# Logic.net
KiCad netlist of a schematic drawn in Altium Designer
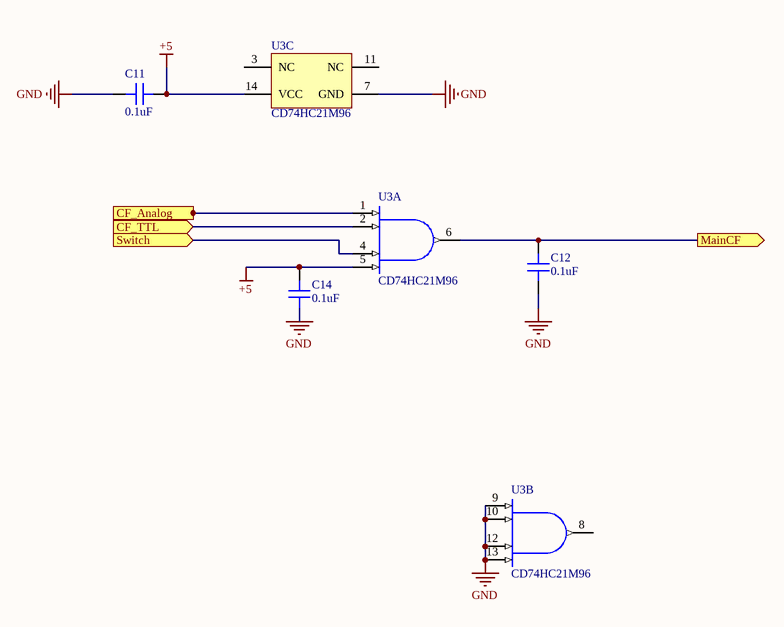
[diagram p0: Logic.SchDoc]

(export (version "E")
  (design (tool "Eeschema 10.0.6"))
  (components
    (comp (ref "C11")
      (value "0.1uF")
      (footprint "CAP 0805/2012")
      (description "CAP CER 0.1UF 25V X7R 0805")
      (fields
        (field (name "PART NUMBER") "CL21B104KACNNNC")
        (field (name "MANUFACTURER") "Samsung Electro-Mechanics America, Inc.")
      )
      (libsource (lib "Celestial Library Database") (part "Capacitor"))
    )
    (comp (ref "C12")
      (value "0.1uF")
      (footprint "CAP 0805/2012")
      (description "CAP CER 0.1UF 25V X7R 0805")
      (fields
        (field (name "PART NUMBER") "CL21B104KACNNNC")
        (field (name "MANUFACTURER") "Samsung Electro-Mechanics America, Inc.")
      )
      (libsource (lib "Celestial Library Database") (part "Capacitor"))
    )
    (comp (ref "C14")
      (value "0.1uF")
      (footprint "CAP 0805/2012")
      (description "CAP CER 0.1UF 25V X7R 0805")
      (fields
        (field (name "PART NUMBER") "CL21B104KACNNNC")
        (field (name "MANUFACTURER") "Samsung Electro-Mechanics America, Inc.")
      )
      (libsource (lib "Celestial Library Database") (part "Capacitor"))
    )
    (comp (ref "U3")
      (value "CD74HC21M96")
      (footprint "D0014A_N")
      (description "High Speed CMOS Logic Dual 4-Input AND Gates, D0014A, LARGE T&R")
      (fields
        (field (name "GENERIC PART NUMBER") "CD74HC21")
        (field (name "MANUFACTURER") "Texas Instruments")
      )
      (libsource (lib "Altium Content Vault") (part "TI-SNX4XXX21X-14"))
    )
  )
  (nets
    (net (code "1") (name "+5") (class "Default")
      (node (ref "C11") (pin "1") (pinfunction "1_1") (pintype "passive"))
      (node (ref "C14") (pin "1") (pinfunction "1_1") (pintype "passive"))
      (node (ref "U3") (pin "14") (pinfunction "VCC_14") (pintype "power_in"))
      (node (ref "U3") (pin "5") (pinfunction "1D_5") (pintype "input"))
    )
    (net (code "2") (name "/CF_Analog") (class "Default")
      (node (ref "U3") (pin "1") (pinfunction "1A_1") (pintype "input"))
    )
    (net (code "3") (name "/CF_TTL") (class "Default")
      (node (ref "U3") (pin "2") (pinfunction "1B_2") (pintype "input"))
    )
    (net (code "4") (name "/MainCF") (class "Default")
      (node (ref "C12") (pin "1") (pinfunction "1_1") (pintype "passive"))
      (node (ref "U3") (pin "6") (pinfunction "1Y_6") (pintype "output"))
    )
    (net (code "5") (name "/Switch") (class "Default")
      (node (ref "U3") (pin "4") (pinfunction "1C_4") (pintype "input"))
    )
    (net (code "6") (name "GND") (class "Default")
      (node (ref "C11") (pin "2") (pinfunction "2_2") (pintype "passive"))
      (node (ref "C12") (pin "2") (pinfunction "2_2") (pintype "passive"))
      (node (ref "C14") (pin "2") (pinfunction "2_2") (pintype "passive"))
      (node (ref "U3") (pin "10") (pinfunction "2B_10") (pintype "input"))
      (node (ref "U3") (pin "12") (pinfunction "2C_12") (pintype "input"))
      (node (ref "U3") (pin "13") (pinfunction "2D_13") (pintype "input"))
      (node (ref "U3") (pin "7") (pinfunction "GND_7") (pintype "power_in"))
      (node (ref "U3") (pin "9") (pinfunction "2A_9") (pintype "input"))
    )
    (net (code "7") (name "unconnected-(U3B-2Y-Pad8)") (class "Default")
      (node (ref "U3") (pin "8") (pinfunction "2Y_8") (pintype "output"))
    )
    (net (code "8") (name "unconnected-(U3C-NC-Pad3)") (class "Default")
      (node (ref "U3") (pin "3") (pinfunction "NC_3") (pintype "passive"))
    )
    (net (code "9") (name "unconnected-(U3C-NC-Pad11)") (class "Default")
      (node (ref "U3") (pin "11") (pinfunction "NC_11") (pintype "passive"))
    )
  )
)
